# RotSense.net
KiCad netlist of a schematic drawn in Altium Designer
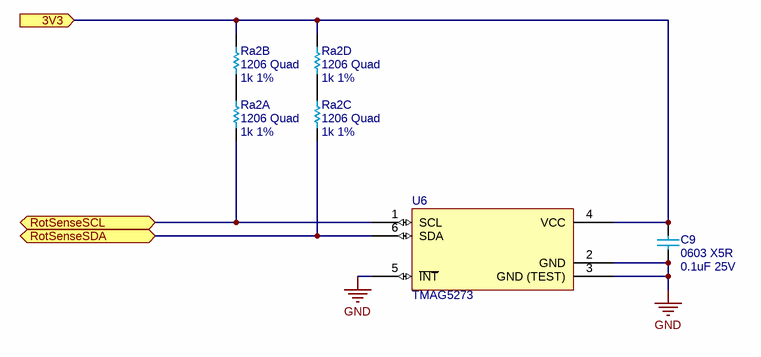
[diagram p0: RotSense.SchDoc]

(export (version "E")
  (design (tool "Eeschema 10.0.6"))
  (components
    (comp (ref "C9")
      (value "0603 X5R")
      (footprint "0603 capacitor - CAPC1608X06N")
      (description "0603, X5R or better")
      (fields (field (name "ALTIUM_VALUE") "0.1uF 25V"))
      (libsource (lib "Chip_Passives") (part "Cap 0.1uF 25V"))
    )
    (comp (ref "Ra2")
      (value "1206 Quad")
      (footprint "4x 1k 1% - CAC-80P320X160-8M")
      (description "Chip resistor")
      (fields (field (name "ALTIUM_VALUE") "1k 1%"))
      (libsource (lib "Chip_Passives") (part "Quad Res 1k 1% 1206"))
    )
    (comp (ref "U6")
      (value "TMAG5273")
      (footprint "TMAG5273 - SOT95P280X145-6M")
      (description "Low-Power Linear 3D Hall-Effect Sensor With I2C Interface")
      (libsource (lib "Sensors") (part "TMAG5273"))
    )
  )
  (nets
    (net (code "1") (name "/3V3") (class "Default")
      (node (ref "C9") (pin "2") (pinfunction "2_2") (pintype "passive"))
      (node (ref "Ra2") (pin "5") (pinfunction "5_5") (pintype "passive"))
      (node (ref "Ra2") (pin "7") (pinfunction "7_7") (pintype "passive"))
      (node (ref "U6") (pin "4") (pinfunction "VCC_4") (pintype "passive"))
    )
    (net (code "2") (name "/RotSenseSCL") (class "Default")
      (node (ref "Ra2") (pin "1") (pinfunction "1_1") (pintype "passive"))
      (node (ref "U6") (pin "1") (pinfunction "SCL_1") (pintype "bidirectional"))
    )
    (net (code "3") (name "/RotSenseSDA") (class "Default")
      (node (ref "Ra2") (pin "3") (pinfunction "3_3") (pintype "passive"))
      (node (ref "U6") (pin "6") (pinfunction "SDA_6") (pintype "bidirectional"))
    )
    (net (code "4") (name "GND") (class "Default")
      (node (ref "C9") (pin "1") (pinfunction "1_1") (pintype "passive"))
      (node (ref "U6") (pin "2") (pinfunction "GND_2") (pintype "passive"))
      (node (ref "U6") (pin "3") (pinfunction "GND_(TEST)_3") (pintype "passive"))
      (node (ref "U6") (pin "5") (pinfunction "~{INT}_5") (pintype "bidirectional"))
    )
    (net (code "5") (name "Net-(Ra2-Pad2)") (class "Default")
      (node (ref "Ra2") (pin "2") (pinfunction "2_2") (pintype "passive"))
      (node (ref "Ra2") (pin "8") (pinfunction "8_8") (pintype "passive"))
    )
    (net (code "6") (name "Net-(Ra2-Pad4)") (class "Default")
      (node (ref "Ra2") (pin "4") (pinfunction "4_4") (pintype "passive"))
      (node (ref "Ra2") (pin "6") (pinfunction "6_6") (pintype "passive"))
    )
  )
)
